# hack.net
KiCad netlist of a schematic drawn in EAGLE
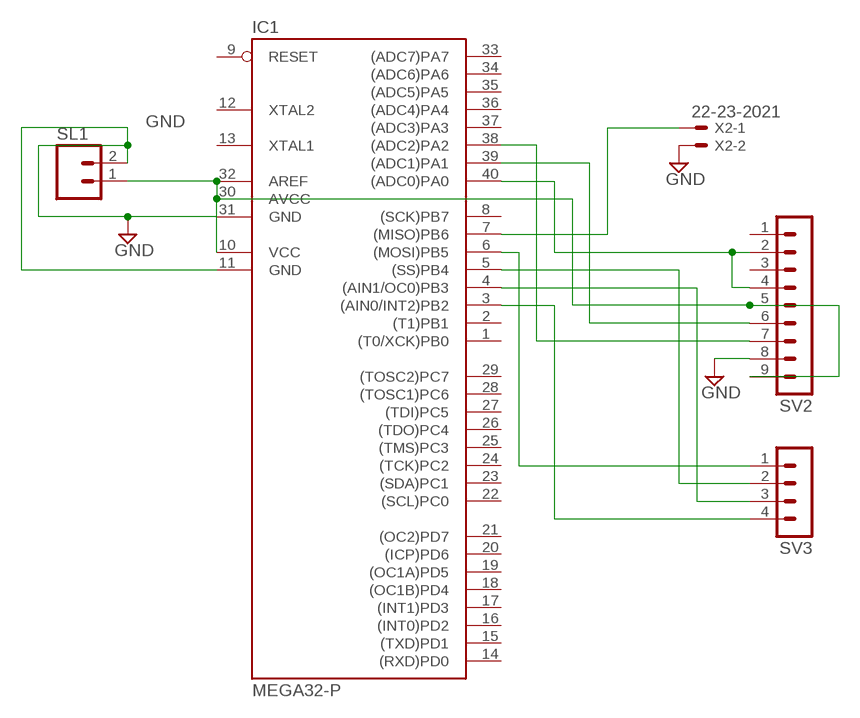
[diagram p0: schematic, sheet 1]

(export (version "E")
  (design (tool "Eeschema 10.0.6"))
  (components
    (comp (ref "IC1")
      (value "MEGA32-P")
      (footprint "eagle-import:DIL40")
      (fields (field (name "MPN") "ATMEGA32-16PU"))
      (libsource (lib "eagle-import") (part "MEGA32-P"))
    )
    (comp (ref "SL1")
      (value "M02")
      (footprint "eagle-import:02P")
      (libsource (lib "eagle-import") (part "M02"))
    )
    (comp (ref "SV2")
      (value "MA09-1W")
      (footprint "eagle-import:MA09-1W")
      (libsource (lib "eagle-import") (part "MA09-1W"))
    )
    (comp (ref "SV3")
      (value "MA04-1")
      (footprint "eagle-import:MA04-1")
      (libsource (lib "eagle-import") (part "MA04-1"))
    )
    (comp (ref "X2")
      (value "22-23-2021")
      (footprint "eagle-import:22-23-2021")
      (fields (field (name "MF") "MOLEX"))
      (libsource (lib "eagle-import") (part "22-23-2021"))
    )
  )
  (nets
    (net (code "1") (name "GND") (class "Default")
      (node (ref "IC1") (pin "11") (pinfunction "GND_11") (pintype "power_in"))
      (node (ref "IC1") (pin "31") (pinfunction "GND_31") (pintype "power_in"))
      (node (ref "SL1") (pin "2") (pinfunction "2_2") (pintype "passive"))
      (node (ref "SV2") (pin "8") (pinfunction "8_8") (pintype "passive"))
      (node (ref "X2") (pin "2") (pinfunction "S_2") (pintype "passive"))
    )
    (net (code "2") (name "Net-(IC1-(ADC0)PA0)") (class "Default")
      (node (ref "IC1") (pin "40") (pinfunction "(ADC0)PA0_40") (pintype "bidirectional"))
      (node (ref "SV2") (pin "2") (pinfunction "2_2") (pintype "passive"))
      (node (ref "SV2") (pin "4") (pinfunction "4_4") (pintype "passive"))
    )
    (net (code "3") (name "Net-(IC1-(ADC1)PA1)") (class "Default")
      (node (ref "IC1") (pin "39") (pinfunction "(ADC1)PA1_39") (pintype "bidirectional"))
      (node (ref "SV2") (pin "6") (pinfunction "6_6") (pintype "passive"))
    )
    (net (code "4") (name "Net-(IC1-(ADC2)PA2)") (class "Default")
      (node (ref "IC1") (pin "38") (pinfunction "(ADC2)PA2_38") (pintype "bidirectional"))
      (node (ref "SV2") (pin "7") (pinfunction "7_7") (pintype "passive"))
    )
    (net (code "5") (name "Net-(IC1-(AIN0{slash}INT2)PB2)") (class "Default")
      (node (ref "IC1") (pin "3") (pinfunction "(AIN0/INT2)PB2_3") (pintype "bidirectional"))
      (node (ref "SV3") (pin "4") (pinfunction "4_4") (pintype "passive"))
    )
    (net (code "6") (name "Net-(IC1-(AIN1{slash}OC0)PB3)") (class "Default")
      (node (ref "IC1") (pin "4") (pinfunction "(AIN1/OC0)PB3_4") (pintype "bidirectional"))
      (node (ref "SV3") (pin "3") (pinfunction "3_3") (pintype "passive"))
    )
    (net (code "7") (name "Net-(IC1-(MISO)PB6)") (class "Default")
      (node (ref "IC1") (pin "7") (pinfunction "(MISO)PB6_7") (pintype "bidirectional"))
      (node (ref "X2") (pin "1") (pinfunction "S_1") (pintype "passive"))
    )
    (net (code "8") (name "Net-(IC1-(MOSI)PB5)") (class "Default")
      (node (ref "IC1") (pin "6") (pinfunction "(MOSI)PB5_6") (pintype "bidirectional"))
      (node (ref "SV3") (pin "1") (pinfunction "1_1") (pintype "passive"))
    )
    (net (code "9") (name "Net-(IC1-(SS)PB4)") (class "Default")
      (node (ref "IC1") (pin "5") (pinfunction "(SS)PB4_5") (pintype "bidirectional"))
      (node (ref "SV3") (pin "2") (pinfunction "2_2") (pintype "passive"))
    )
    (net (code "10") (name "Net-(IC1-AREF)") (class "Default")
      (node (ref "IC1") (pin "10") (pinfunction "VCC_10") (pintype "power_in"))
      (node (ref "IC1") (pin "30") (pinfunction "AVCC_30") (pintype "power_in"))
      (node (ref "IC1") (pin "32") (pinfunction "AREF_32") (pintype "passive"))
      (node (ref "SL1") (pin "1") (pinfunction "1_1") (pintype "passive"))
      (node (ref "SV2") (pin "5") (pinfunction "5_5") (pintype "passive"))
      (node (ref "SV2") (pin "9") (pinfunction "9_9") (pintype "passive"))
    )
    (net (code "11") (name "unconnected-(IC1-(ADC3)PA3-Pad37)") (class "Default")
      (node (ref "IC1") (pin "37") (pinfunction "(ADC3)PA3_37") (pintype "bidirectional"))
    )
    (net (code "12") (name "unconnected-(IC1-(ADC4)PA4-Pad36)") (class "Default")
      (node (ref "IC1") (pin "36") (pinfunction "(ADC4)PA4_36") (pintype "bidirectional"))
    )
    (net (code "13") (name "unconnected-(IC1-(ADC5)PA5-Pad35)") (class "Default")
      (node (ref "IC1") (pin "35") (pinfunction "(ADC5)PA5_35") (pintype "bidirectional"))
    )
    (net (code "14") (name "unconnected-(IC1-(ADC6)PA6-Pad34)") (class "Default")
      (node (ref "IC1") (pin "34") (pinfunction "(ADC6)PA6_34") (pintype "bidirectional"))
    )
    (net (code "15") (name "unconnected-(IC1-(ADC7)PA7-Pad33)") (class "Default")
      (node (ref "IC1") (pin "33") (pinfunction "(ADC7)PA7_33") (pintype "bidirectional"))
    )
    (net (code "16") (name "unconnected-(IC1-(ICP)PD6-Pad20)") (class "Default")
      (node (ref "IC1") (pin "20") (pinfunction "(ICP)PD6_20") (pintype "bidirectional"))
    )
    (net (code "17") (name "unconnected-(IC1-(INT0)PD2-Pad16)") (class "Default")
      (node (ref "IC1") (pin "16") (pinfunction "(INT0)PD2_16") (pintype "bidirectional"))
    )
    (net (code "18") (name "unconnected-(IC1-(INT1)PD3-Pad17)") (class "Default")
      (node (ref "IC1") (pin "17") (pinfunction "(INT1)PD3_17") (pintype "bidirectional"))
    )
    (net (code "19") (name "unconnected-(IC1-(OC1A)PD5-Pad19)") (class "Default")
      (node (ref "IC1") (pin "19") (pinfunction "(OC1A)PD5_19") (pintype "bidirectional"))
    )
    (net (code "20") (name "unconnected-(IC1-(OC1B)PD4-Pad18)") (class "Default")
      (node (ref "IC1") (pin "18") (pinfunction "(OC1B)PD4_18") (pintype "bidirectional"))
    )
    (net (code "21") (name "unconnected-(IC1-(OC2)PD7-Pad21)") (class "Default")
      (node (ref "IC1") (pin "21") (pinfunction "(OC2)PD7_21") (pintype "bidirectional"))
    )
    (net (code "22") (name "unconnected-(IC1-(RXD)PD0-Pad14)") (class "Default")
      (node (ref "IC1") (pin "14") (pinfunction "(RXD)PD0_14") (pintype "bidirectional"))
    )
    (net (code "23") (name "unconnected-(IC1-(SCK)PB7-Pad8)") (class "Default")
      (node (ref "IC1") (pin "8") (pinfunction "(SCK)PB7_8") (pintype "bidirectional"))
    )
    (net (code "24") (name "unconnected-(IC1-(SCL)PC0-Pad22)") (class "Default")
      (node (ref "IC1") (pin "22") (pinfunction "(SCL)PC0_22") (pintype "bidirectional"))
    )
    (net (code "25") (name "unconnected-(IC1-(SDA)PC1-Pad23)") (class "Default")
      (node (ref "IC1") (pin "23") (pinfunction "(SDA)PC1_23") (pintype "bidirectional"))
    )
    (net (code "26") (name "unconnected-(IC1-(T0{slash}XCK)PB0-Pad1)") (class "Default")
      (node (ref "IC1") (pin "1") (pinfunction "(T0/XCK)PB0_1") (pintype "bidirectional"))
    )
    (net (code "27") (name "unconnected-(IC1-(T1)PB1-Pad2)") (class "Default")
      (node (ref "IC1") (pin "2") (pinfunction "(T1)PB1_2") (pintype "bidirectional"))
    )
    (net (code "28") (name "unconnected-(IC1-(TCK)PC2-Pad24)") (class "Default")
      (node (ref "IC1") (pin "24") (pinfunction "(TCK)PC2_24") (pintype "bidirectional"))
    )
    (net (code "29") (name "unconnected-(IC1-(TDI)PC5-Pad27)") (class "Default")
      (node (ref "IC1") (pin "27") (pinfunction "(TDI)PC5_27") (pintype "bidirectional"))
    )
    (net (code "30") (name "unconnected-(IC1-(TDO)PC4-Pad26)") (class "Default")
      (node (ref "IC1") (pin "26") (pinfunction "(TDO)PC4_26") (pintype "bidirectional"))
    )
    (net (code "31") (name "unconnected-(IC1-(TMS)PC3-Pad25)") (class "Default")
      (node (ref "IC1") (pin "25") (pinfunction "(TMS)PC3_25") (pintype "bidirectional"))
    )
    (net (code "32") (name "unconnected-(IC1-(TOSC1)PC6-Pad28)") (class "Default")
      (node (ref "IC1") (pin "28") (pinfunction "(TOSC1)PC6_28") (pintype "bidirectional"))
    )
    (net (code "33") (name "unconnected-(IC1-(TOSC2)PC7-Pad29)") (class "Default")
      (node (ref "IC1") (pin "29") (pinfunction "(TOSC2)PC7_29") (pintype "bidirectional"))
    )
    (net (code "34") (name "unconnected-(IC1-(TXD)PD1-Pad15)") (class "Default")
      (node (ref "IC1") (pin "15") (pinfunction "(TXD)PD1_15") (pintype "bidirectional"))
    )
    (net (code "35") (name "unconnected-(IC1-RESET-Pad9)") (class "Default")
      (node (ref "IC1") (pin "9") (pinfunction "RESET_9") (pintype "input"))
    )
    (net (code "36") (name "unconnected-(IC1-XTAL1-Pad13)") (class "Default")
      (node (ref "IC1") (pin "13") (pinfunction "XTAL1_13") (pintype "bidirectional"))
    )
    (net (code "37") (name "unconnected-(IC1-XTAL2-Pad12)") (class "Default")
      (node (ref "IC1") (pin "12") (pinfunction "XTAL2_12") (pintype "bidirectional"))
    )
    (net (code "38") (name "unconnected-(SV2-Pad1)") (class "Default")
      (node (ref "SV2") (pin "1") (pinfunction "1_1") (pintype "passive"))
    )
    (net (code "39") (name "unconnected-(SV2-Pad3)") (class "Default")
      (node (ref "SV2") (pin "3") (pinfunction "3_3") (pintype "passive"))
    )
  )
)
